# LED.net
KiCad netlist of a schematic drawn in EAGLE
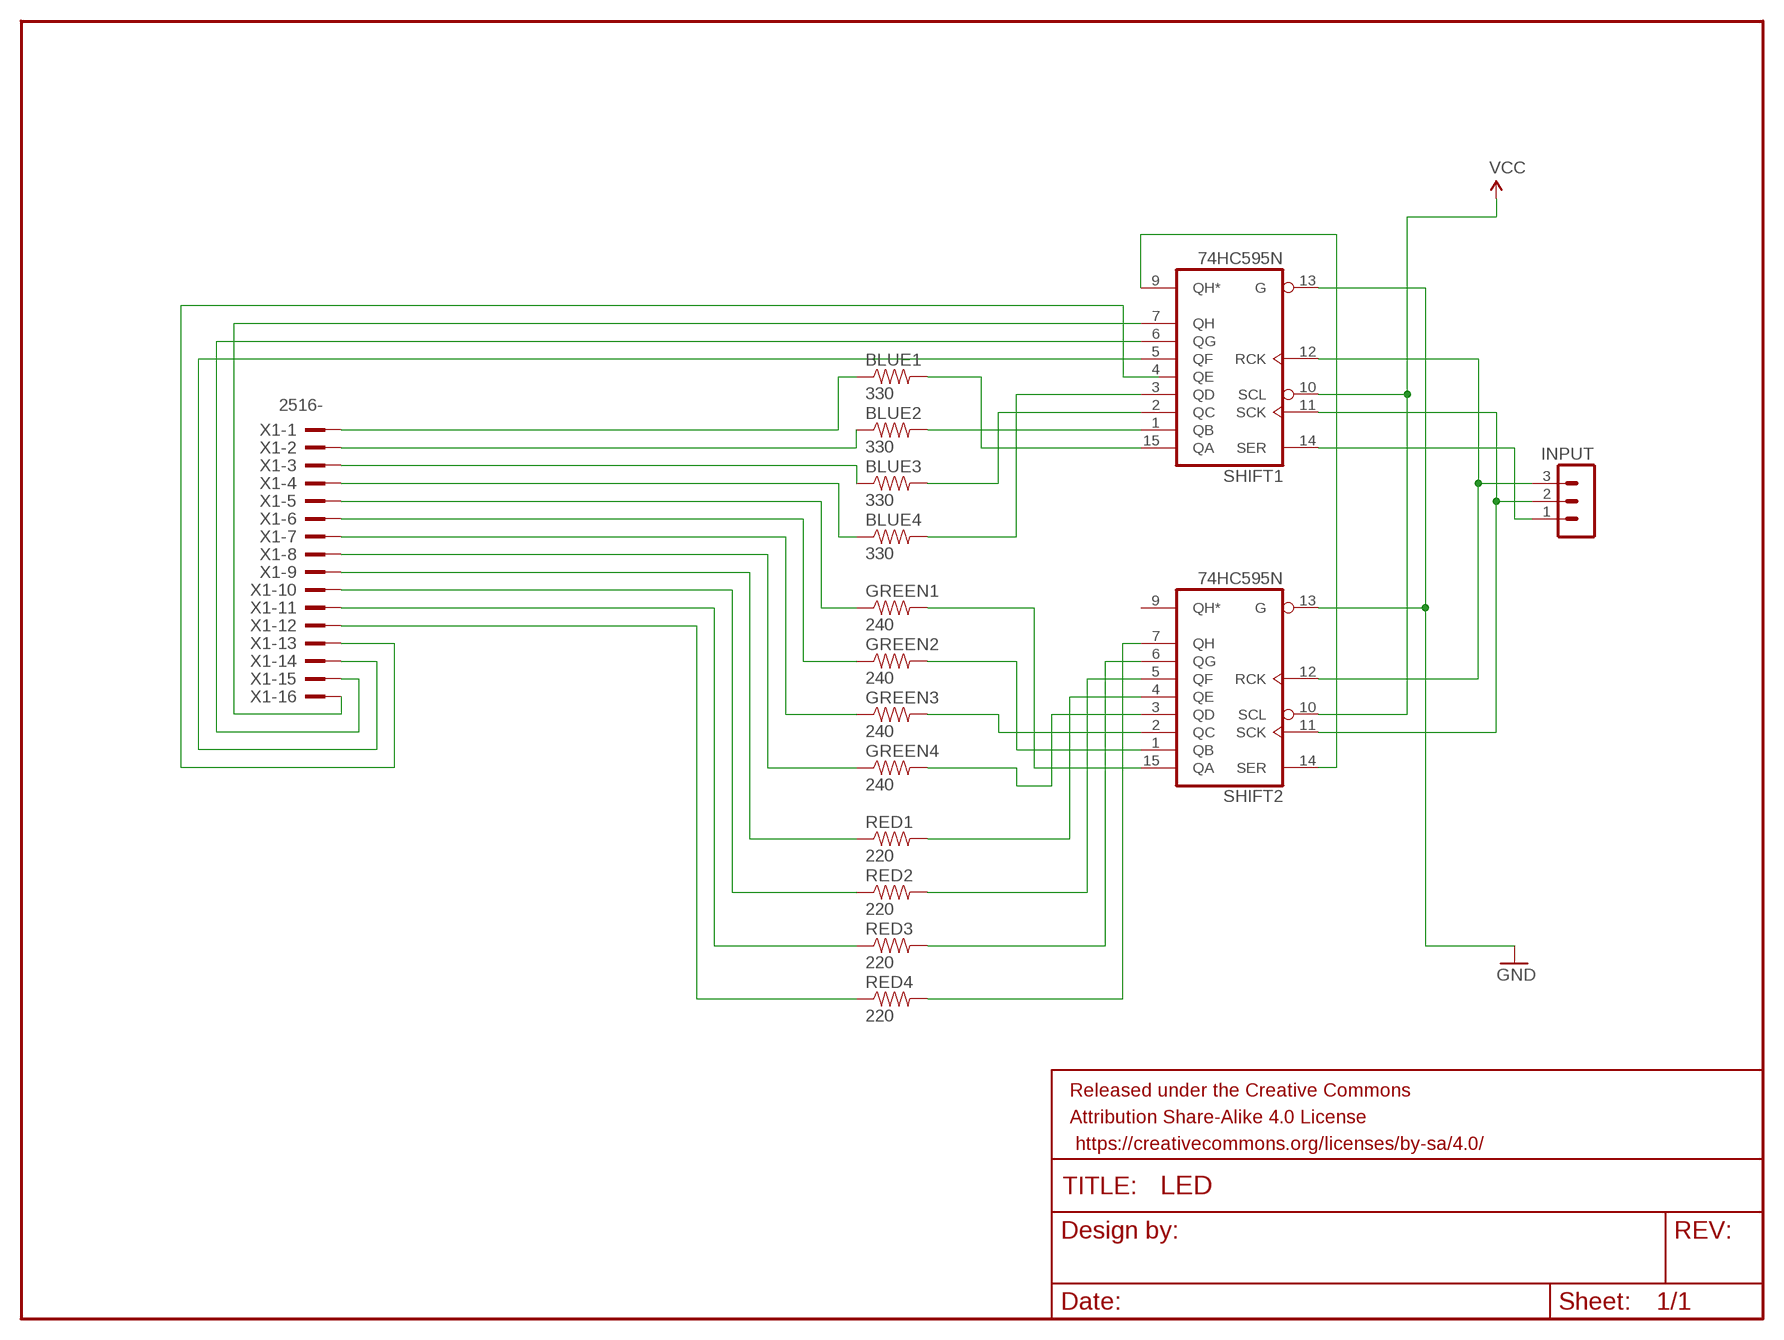
[diagram p0: schematic, sheet 1]

(export (version "E")
  (design (tool "Eeschema 10.0.6"))
  (components
    (comp (ref "BLUE1")
      (value "330")
      (footprint "eagle-import:AXIAL-0.3EZ")
      (libsource (lib "eagle-import") (part "RESISTOREZ"))
    )
    (comp (ref "BLUE2")
      (value "330")
      (footprint "eagle-import:AXIAL-0.3EZ")
      (libsource (lib "eagle-import") (part "RESISTOREZ"))
    )
    (comp (ref "BLUE3")
      (value "330")
      (footprint "eagle-import:AXIAL-0.3EZ")
      (libsource (lib "eagle-import") (part "RESISTOREZ"))
    )
    (comp (ref "BLUE4")
      (value "330")
      (footprint "eagle-import:AXIAL-0.3EZ")
      (libsource (lib "eagle-import") (part "RESISTOREZ"))
    )
    (comp (ref "FRAME1")
      (value "FRAME-LETTER")
      (footprint "eagle-import:CREATIVE_COMMONS")
      (libsource (lib "eagle-import") (part "FRAME-LETTER"))
    )
    (comp (ref "GREEN1")
      (value "240")
      (footprint "eagle-import:AXIAL-0.3EZ")
      (libsource (lib "eagle-import") (part "RESISTOREZ"))
    )
    (comp (ref "GREEN2")
      (value "240")
      (footprint "eagle-import:AXIAL-0.3EZ")
      (libsource (lib "eagle-import") (part "RESISTOREZ"))
    )
    (comp (ref "GREEN3")
      (value "240")
      (footprint "eagle-import:AXIAL-0.3EZ")
      (libsource (lib "eagle-import") (part "RESISTOREZ"))
    )
    (comp (ref "GREEN4")
      (value "240")
      (footprint "eagle-import:AXIAL-0.3EZ")
      (libsource (lib "eagle-import") (part "RESISTOREZ"))
    )
    (comp (ref "INPUT")
      (value "MA03-1")
      (footprint "eagle-import:MA03-1")
      (libsource (lib "eagle-import") (part "MA03-1"))
    )
    (comp (ref "RED1")
      (value "220")
      (footprint "eagle-import:AXIAL-0.3EZ")
      (libsource (lib "eagle-import") (part "RESISTOREZ"))
    )
    (comp (ref "RED2")
      (value "220")
      (footprint "eagle-import:AXIAL-0.3EZ")
      (libsource (lib "eagle-import") (part "RESISTOREZ"))
    )
    (comp (ref "RED3")
      (value "220")
      (footprint "eagle-import:AXIAL-0.3EZ")
      (libsource (lib "eagle-import") (part "RESISTOREZ"))
    )
    (comp (ref "RED4")
      (value "220")
      (footprint "eagle-import:AXIAL-0.3EZ")
      (libsource (lib "eagle-import") (part "RESISTOREZ"))
    )
    (comp (ref "SHIFT1")
      (value "74HC595N")
      (footprint "eagle-import:DIL16")
      (libsource (lib "eagle-import") (part "74595NHC"))
    )
    (comp (ref "SHIFT2")
      (value "74HC595N")
      (footprint "eagle-import:DIL16")
      (libsource (lib "eagle-import") (part "74595NHC"))
    )
    (comp (ref "X1")
      (value "2516-")
      (footprint "eagle-import:PAK100_2500-16")
      (libsource (lib "eagle-import") (part "2516-"))
    )
  )
  (nets
    (net (code "1") (name "GND") (class "Default")
      (node (ref "SHIFT1") (pin "13") (pinfunction "G_13") (pintype "input"))
      (node (ref "SHIFT2") (pin "13") (pinfunction "G_13") (pintype "input"))
    )
    (net (code "2") (name "Net-(BLUE1-1)") (class "Default")
      (node (ref "BLUE1") (pin "P$1") (pinfunction "1_P$1") (pintype "passive"))
      (node (ref "X1") (pin "1") (pinfunction "KL_1") (pintype "passive"))
    )
    (net (code "3") (name "Net-(BLUE1-2)") (class "Default")
      (node (ref "BLUE1") (pin "P$2") (pinfunction "2_P$2") (pintype "passive"))
      (node (ref "SHIFT1") (pin "15") (pinfunction "QA_15") (pintype "tri_state"))
    )
    (net (code "4") (name "Net-(BLUE2-1)") (class "Default")
      (node (ref "BLUE2") (pin "P$1") (pinfunction "1_P$1") (pintype "passive"))
      (node (ref "X1") (pin "2") (pinfunction "KL_2") (pintype "passive"))
    )
    (net (code "5") (name "Net-(BLUE2-2)") (class "Default")
      (node (ref "BLUE2") (pin "P$2") (pinfunction "2_P$2") (pintype "passive"))
      (node (ref "SHIFT1") (pin "1") (pinfunction "QB_1") (pintype "tri_state"))
    )
    (net (code "6") (name "Net-(BLUE3-1)") (class "Default")
      (node (ref "BLUE3") (pin "P$1") (pinfunction "1_P$1") (pintype "passive"))
      (node (ref "X1") (pin "3") (pinfunction "KL_3") (pintype "passive"))
    )
    (net (code "7") (name "Net-(BLUE3-2)") (class "Default")
      (node (ref "BLUE3") (pin "P$2") (pinfunction "2_P$2") (pintype "passive"))
      (node (ref "SHIFT1") (pin "2") (pinfunction "QC_2") (pintype "tri_state"))
    )
    (net (code "8") (name "Net-(BLUE4-1)") (class "Default")
      (node (ref "BLUE4") (pin "P$1") (pinfunction "1_P$1") (pintype "passive"))
      (node (ref "X1") (pin "4") (pinfunction "KL_4") (pintype "passive"))
    )
    (net (code "9") (name "Net-(BLUE4-2)") (class "Default")
      (node (ref "BLUE4") (pin "P$2") (pinfunction "2_P$2") (pintype "passive"))
      (node (ref "SHIFT1") (pin "3") (pinfunction "QD_3") (pintype "tri_state"))
    )
    (net (code "10") (name "Net-(GREEN1-1)") (class "Default")
      (node (ref "GREEN1") (pin "P$1") (pinfunction "1_P$1") (pintype "passive"))
      (node (ref "X1") (pin "5") (pinfunction "KL_5") (pintype "passive"))
    )
    (net (code "11") (name "Net-(GREEN1-2)") (class "Default")
      (node (ref "GREEN1") (pin "P$2") (pinfunction "2_P$2") (pintype "passive"))
      (node (ref "SHIFT2") (pin "15") (pinfunction "QA_15") (pintype "tri_state"))
    )
    (net (code "12") (name "Net-(GREEN2-1)") (class "Default")
      (node (ref "GREEN2") (pin "P$1") (pinfunction "1_P$1") (pintype "passive"))
      (node (ref "X1") (pin "6") (pinfunction "KL_6") (pintype "passive"))
    )
    (net (code "13") (name "Net-(GREEN2-2)") (class "Default")
      (node (ref "GREEN2") (pin "P$2") (pinfunction "2_P$2") (pintype "passive"))
      (node (ref "SHIFT2") (pin "1") (pinfunction "QB_1") (pintype "tri_state"))
    )
    (net (code "14") (name "Net-(GREEN3-1)") (class "Default")
      (node (ref "GREEN3") (pin "P$1") (pinfunction "1_P$1") (pintype "passive"))
      (node (ref "X1") (pin "7") (pinfunction "KL_7") (pintype "passive"))
    )
    (net (code "15") (name "Net-(GREEN3-2)") (class "Default")
      (node (ref "GREEN3") (pin "P$2") (pinfunction "2_P$2") (pintype "passive"))
      (node (ref "SHIFT2") (pin "2") (pinfunction "QC_2") (pintype "tri_state"))
    )
    (net (code "16") (name "Net-(GREEN4-1)") (class "Default")
      (node (ref "GREEN4") (pin "P$1") (pinfunction "1_P$1") (pintype "passive"))
      (node (ref "X1") (pin "8") (pinfunction "KL_8") (pintype "passive"))
    )
    (net (code "17") (name "Net-(GREEN4-2)") (class "Default")
      (node (ref "GREEN4") (pin "P$2") (pinfunction "2_P$2") (pintype "passive"))
      (node (ref "SHIFT2") (pin "3") (pinfunction "QD_3") (pintype "tri_state"))
    )
    (net (code "18") (name "Net-(RED1-1)") (class "Default")
      (node (ref "RED1") (pin "P$1") (pinfunction "1_P$1") (pintype "passive"))
      (node (ref "X1") (pin "9") (pinfunction "KL_9") (pintype "passive"))
    )
    (net (code "19") (name "Net-(RED1-2)") (class "Default")
      (node (ref "RED1") (pin "P$2") (pinfunction "2_P$2") (pintype "passive"))
      (node (ref "SHIFT2") (pin "4") (pinfunction "QE_4") (pintype "tri_state"))
    )
    (net (code "20") (name "Net-(RED2-1)") (class "Default")
      (node (ref "RED2") (pin "P$1") (pinfunction "1_P$1") (pintype "passive"))
      (node (ref "X1") (pin "10") (pinfunction "KL_10") (pintype "passive"))
    )
    (net (code "21") (name "Net-(RED2-2)") (class "Default")
      (node (ref "RED2") (pin "P$2") (pinfunction "2_P$2") (pintype "passive"))
      (node (ref "SHIFT2") (pin "5") (pinfunction "QF_5") (pintype "tri_state"))
    )
    (net (code "22") (name "Net-(RED3-1)") (class "Default")
      (node (ref "RED3") (pin "P$1") (pinfunction "1_P$1") (pintype "passive"))
      (node (ref "X1") (pin "11") (pinfunction "KL_11") (pintype "passive"))
    )
    (net (code "23") (name "Net-(RED3-2)") (class "Default")
      (node (ref "RED3") (pin "P$2") (pinfunction "2_P$2") (pintype "passive"))
      (node (ref "SHIFT2") (pin "6") (pinfunction "QG_6") (pintype "tri_state"))
    )
    (net (code "24") (name "Net-(RED4-1)") (class "Default")
      (node (ref "RED4") (pin "P$1") (pinfunction "1_P$1") (pintype "passive"))
      (node (ref "X1") (pin "12") (pinfunction "KL_12") (pintype "passive"))
    )
    (net (code "25") (name "Net-(RED4-2)") (class "Default")
      (node (ref "RED4") (pin "P$2") (pinfunction "2_P$2") (pintype "passive"))
      (node (ref "SHIFT2") (pin "7") (pinfunction "QH_7") (pintype "tri_state"))
    )
    (net (code "26") (name "Net-(SHIFT1A-QF)") (class "Default")
      (node (ref "SHIFT1") (pin "5") (pinfunction "QF_5") (pintype "tri_state"))
      (node (ref "X1") (pin "14") (pinfunction "KL_14") (pintype "passive"))
    )
    (net (code "27") (name "Net-(SHIFT1A-QG)") (class "Default")
      (node (ref "SHIFT1") (pin "6") (pinfunction "QG_6") (pintype "tri_state"))
      (node (ref "X1") (pin "15") (pinfunction "KL_15") (pintype "passive"))
    )
    (net (code "28") (name "Net-(SHIFT1A-QH)") (class "Default")
      (node (ref "SHIFT1") (pin "7") (pinfunction "QH_7") (pintype "tri_state"))
      (node (ref "X1") (pin "16") (pinfunction "KL_16") (pintype "passive"))
    )
    (net (code "29") (name "Net-(SHIFT1A-QH*)") (class "Default")
      (node (ref "SHIFT1") (pin "9") (pinfunction "QH*_9") (pintype "tri_state"))
      (node (ref "SHIFT2") (pin "14") (pinfunction "SER_14") (pintype "input"))
    )
    (net (code "30") (name "Net-(SHIFT1A-RCK)") (class "Default")
      (node (ref "INPUT") (pin "3") (pinfunction "3_3") (pintype "passive"))
      (node (ref "SHIFT1") (pin "12") (pinfunction "RCK_12") (pintype "input"))
      (node (ref "SHIFT2") (pin "12") (pinfunction "RCK_12") (pintype "input"))
    )
    (net (code "31") (name "Net-(SHIFT1A-SCK)") (class "Default")
      (node (ref "INPUT") (pin "2") (pinfunction "2_2") (pintype "passive"))
      (node (ref "SHIFT1") (pin "11") (pinfunction "SCK_11") (pintype "input"))
      (node (ref "SHIFT2") (pin "11") (pinfunction "SCK_11") (pintype "input"))
    )
    (net (code "32") (name "Net-(SHIFT1A-SER)") (class "Default")
      (node (ref "INPUT") (pin "1") (pinfunction "1_1") (pintype "passive"))
      (node (ref "SHIFT1") (pin "14") (pinfunction "SER_14") (pintype "input"))
    )
    (net (code "33") (name "VCC") (class "Default")
      (node (ref "SHIFT1") (pin "10") (pinfunction "SCL_10") (pintype "input"))
      (node (ref "SHIFT2") (pin "10") (pinfunction "SCL_10") (pintype "input"))
    )
    (net (code "34") (name "unconnected-(SHIFT1A-QE-Pad4)") (class "Default")
      (node (ref "SHIFT1") (pin "4") (pinfunction "QE_4") (pintype "tri_state"))
    )
    (net (code "35") (name "unconnected-(SHIFT2A-QH*-Pad9)") (class "Default")
      (node (ref "SHIFT2") (pin "9") (pinfunction "QH*_9") (pintype "tri_state"))
    )
    (net (code "36") (name "unconnected-(X1E-KL-Pad13)") (class "Default")
      (node (ref "X1") (pin "13") (pinfunction "KL_13") (pintype "passive"))
    )
  )
)
